# tec_controller_v3.net
KiCad netlist of a schematic drawn in EAGLE
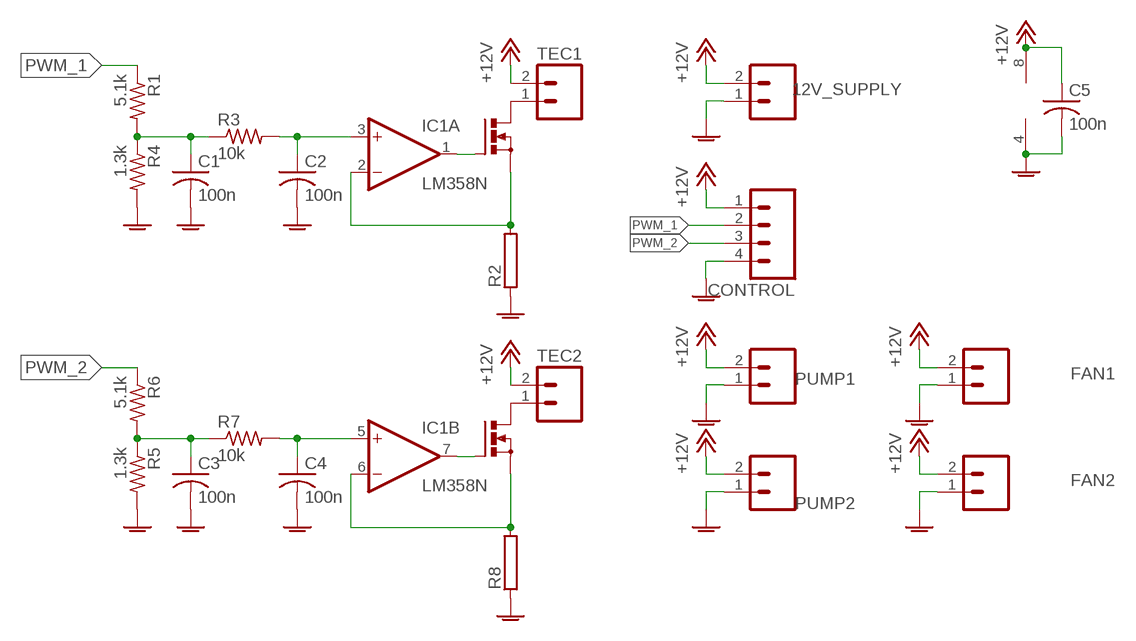
[diagram p0: schematic, sheet 1]

(export (version "E")
  (design (tool "Eeschema 10.0.6"))
  (components
    (comp (ref "12V_SUPPLY")
      (value "M02LOCK_LONGPADS")
      (footprint "eagle-import:1X02_LOCK_LONGPADS")
      (libsource (lib "eagle-import") (part "M02LOCK_LONGPADS"))
    )
    (comp (ref "C1")
      (value "100n")
      (footprint "eagle-import:C0805")
      (libsource (lib "eagle-import") (part "C-USC0805"))
    )
    (comp (ref "C2")
      (value "100n")
      (footprint "eagle-import:C0805")
      (libsource (lib "eagle-import") (part "C-USC0805"))
    )
    (comp (ref "C3")
      (value "100n")
      (footprint "eagle-import:C0805")
      (libsource (lib "eagle-import") (part "C-USC0805"))
    )
    (comp (ref "C4")
      (value "100n")
      (footprint "eagle-import:C0805")
      (libsource (lib "eagle-import") (part "C-USC0805"))
    )
    (comp (ref "C5")
      (value "100n")
      (footprint "eagle-import:C0805")
      (libsource (lib "eagle-import") (part "C-USC0805"))
    )
    (comp (ref "CONTROL")
      (value "M04POLAR")
      (footprint "eagle-import:MOLEX-1X4")
      (libsource (lib "eagle-import") (part "M04POLAR"))
    )
    (comp (ref "FAN1")
      (value "M02LOCK_LONGPADS")
      (footprint "eagle-import:1X02_LOCK_LONGPADS")
      (libsource (lib "eagle-import") (part "M02LOCK_LONGPADS"))
    )
    (comp (ref "FAN2")
      (value "M02LOCK_LONGPADS")
      (footprint "eagle-import:1X02_LOCK_LONGPADS")
      (libsource (lib "eagle-import") (part "M02LOCK_LONGPADS"))
    )
    (comp (ref "IC1")
      (value "LM358N")
      (footprint "eagle-import:DIL08")
      (libsource (lib "eagle-import") (part "LM358N"))
    )
    (comp (ref "PUMP1")
      (value "M02LOCK_LONGPADS")
      (footprint "eagle-import:1X02_LOCK_LONGPADS")
      (libsource (lib "eagle-import") (part "M02LOCK_LONGPADS"))
    )
    (comp (ref "PUMP2")
      (value "M02LOCK_LONGPADS")
      (footprint "eagle-import:1X02_LOCK_LONGPADS")
      (libsource (lib "eagle-import") (part "M02LOCK_LONGPADS"))
    )
    (comp (ref "Q1")
      (value "IRF512")
      (footprint "eagle-import:TO220BV")
      (libsource (lib "eagle-import") (part "IRF512"))
    )
    (comp (ref "Q2")
      (value "IRF512")
      (footprint "eagle-import:TO220BV")
      (libsource (lib "eagle-import") (part "IRF512"))
    )
    (comp (ref "R1")
      (value "5.1k")
      (footprint "eagle-import:M0805")
      (libsource (lib "eagle-import") (part "R-US_M0805"))
    )
    (comp (ref "R2")
      (value "RAC10")
      (footprint "eagle-import:AC10")
      (libsource (lib "eagle-import") (part "RAC10"))
    )
    (comp (ref "R3")
      (value "10k")
      (footprint "eagle-import:M0805")
      (libsource (lib "eagle-import") (part "R-US_M0805"))
    )
    (comp (ref "R4")
      (value "1.3k")
      (footprint "eagle-import:M0805")
      (libsource (lib "eagle-import") (part "R-US_M0805"))
    )
    (comp (ref "R5")
      (value "1.3k")
      (footprint "eagle-import:M0805")
      (libsource (lib "eagle-import") (part "R-US_M0805"))
    )
    (comp (ref "R6")
      (value "5.1k")
      (footprint "eagle-import:M0805")
      (libsource (lib "eagle-import") (part "R-US_M0805"))
    )
    (comp (ref "R7")
      (value "10k")
      (footprint "eagle-import:M0805")
      (libsource (lib "eagle-import") (part "R-US_M0805"))
    )
    (comp (ref "R8")
      (value "RAC10")
      (footprint "eagle-import:AC10")
      (libsource (lib "eagle-import") (part "RAC10"))
    )
    (comp (ref "TEC1")
      (value "M02LOCK_LONGPADS")
      (footprint "eagle-import:1X02_LOCK_LONGPADS")
      (libsource (lib "eagle-import") (part "M02LOCK_LONGPADS"))
    )
    (comp (ref "TEC2")
      (value "M02LOCK_LONGPADS")
      (footprint "eagle-import:1X02_LOCK_LONGPADS")
      (libsource (lib "eagle-import") (part "M02LOCK_LONGPADS"))
    )
  )
  (nets
    (net (code "1") (name "+12V") (class "Default")
      (node (ref "12V_SUPPLY") (pin "2") (pinfunction "2_2") (pintype "passive"))
      (node (ref "C5") (pin "1") (pinfunction "1_1") (pintype "passive"))
      (node (ref "CONTROL") (pin "1") (pinfunction "1_1") (pintype "passive"))
      (node (ref "FAN1") (pin "2") (pinfunction "2_2") (pintype "passive"))
      (node (ref "FAN2") (pin "2") (pinfunction "2_2") (pintype "passive"))
      (node (ref "IC1") (pin "8") (pinfunction "V+_8") (pintype "power_in"))
      (node (ref "PUMP1") (pin "2") (pinfunction "2_2") (pintype "passive"))
      (node (ref "PUMP2") (pin "2") (pinfunction "2_2") (pintype "passive"))
      (node (ref "TEC1") (pin "2") (pinfunction "2_2") (pintype "passive"))
      (node (ref "TEC2") (pin "2") (pinfunction "2_2") (pintype "passive"))
    )
    (net (code "2") (name "GNDA") (class "Default")
      (node (ref "12V_SUPPLY") (pin "1") (pinfunction "1_1") (pintype "passive"))
      (node (ref "C1") (pin "2") (pinfunction "2_2") (pintype "passive"))
      (node (ref "C2") (pin "2") (pinfunction "2_2") (pintype "passive"))
      (node (ref "C3") (pin "2") (pinfunction "2_2") (pintype "passive"))
      (node (ref "C4") (pin "2") (pinfunction "2_2") (pintype "passive"))
      (node (ref "C5") (pin "2") (pinfunction "2_2") (pintype "passive"))
      (node (ref "CONTROL") (pin "4") (pinfunction "4_4") (pintype "passive"))
      (node (ref "FAN1") (pin "1") (pinfunction "1_1") (pintype "passive"))
      (node (ref "FAN2") (pin "1") (pinfunction "1_1") (pintype "passive"))
      (node (ref "IC1") (pin "4") (pinfunction "V-_4") (pintype "power_in"))
      (node (ref "PUMP1") (pin "1") (pinfunction "1_1") (pintype "passive"))
      (node (ref "PUMP2") (pin "1") (pinfunction "1_1") (pintype "passive"))
      (node (ref "R2") (pin "1") (pinfunction "1_1") (pintype "passive"))
      (node (ref "R4") (pin "2") (pinfunction "2_2") (pintype "passive"))
      (node (ref "R5") (pin "2") (pinfunction "2_2") (pintype "passive"))
      (node (ref "R8") (pin "1") (pinfunction "1_1") (pintype "passive"))
    )
    (net (code "3") (name "Net-(C1-Pad1)") (class "Default")
      (node (ref "C1") (pin "1") (pinfunction "1_1") (pintype "passive"))
      (node (ref "R1") (pin "2") (pinfunction "2_2") (pintype "passive"))
      (node (ref "R3") (pin "1") (pinfunction "1_1") (pintype "passive"))
      (node (ref "R4") (pin "1") (pinfunction "1_1") (pintype "passive"))
    )
    (net (code "4") (name "Net-(C3-Pad1)") (class "Default")
      (node (ref "C3") (pin "1") (pinfunction "1_1") (pintype "passive"))
      (node (ref "R5") (pin "1") (pinfunction "1_1") (pintype "passive"))
      (node (ref "R6") (pin "2") (pinfunction "2_2") (pintype "passive"))
      (node (ref "R7") (pin "1") (pinfunction "1_1") (pintype "passive"))
    )
    (net (code "5") (name "Net-(IC1A-+IN)") (class "Default")
      (node (ref "C2") (pin "1") (pinfunction "1_1") (pintype "passive"))
      (node (ref "IC1") (pin "3") (pinfunction "+IN_3") (pintype "input"))
      (node (ref "R3") (pin "2") (pinfunction "2_2") (pintype "passive"))
    )
    (net (code "6") (name "Net-(IC1A--IN)") (class "Default")
      (node (ref "IC1") (pin "2") (pinfunction "-IN_2") (pintype "input"))
      (node (ref "Q1") (pin "S") (pinfunction "S_S") (pintype "passive"))
      (node (ref "R2") (pin "2") (pinfunction "2_2") (pintype "passive"))
    )
    (net (code "7") (name "Net-(IC1A-OUT)") (class "Default")
      (node (ref "IC1") (pin "1") (pinfunction "OUT_1") (pintype "output"))
      (node (ref "Q1") (pin "G") (pinfunction "G_G") (pintype "passive"))
    )
    (net (code "8") (name "Net-(IC1B-+IN)") (class "Default")
      (node (ref "C4") (pin "1") (pinfunction "1_1") (pintype "passive"))
      (node (ref "IC1") (pin "5") (pinfunction "+IN_5") (pintype "input"))
      (node (ref "R7") (pin "2") (pinfunction "2_2") (pintype "passive"))
    )
    (net (code "9") (name "Net-(IC1B--IN)") (class "Default")
      (node (ref "IC1") (pin "6") (pinfunction "-IN_6") (pintype "input"))
      (node (ref "Q2") (pin "S") (pinfunction "S_S") (pintype "passive"))
      (node (ref "R8") (pin "2") (pinfunction "2_2") (pintype "passive"))
    )
    (net (code "10") (name "Net-(IC1B-OUT)") (class "Default")
      (node (ref "IC1") (pin "7") (pinfunction "OUT_7") (pintype "output"))
      (node (ref "Q2") (pin "G") (pinfunction "G_G") (pintype "passive"))
    )
    (net (code "11") (name "Net-(Q1-PadD)") (class "Default")
      (node (ref "Q1") (pin "D") (pinfunction "D_D") (pintype "passive"))
      (node (ref "TEC1") (pin "1") (pinfunction "1_1") (pintype "passive"))
    )
    (net (code "12") (name "Net-(Q2-PadD)") (class "Default")
      (node (ref "Q2") (pin "D") (pinfunction "D_D") (pintype "passive"))
      (node (ref "TEC2") (pin "1") (pinfunction "1_1") (pintype "passive"))
    )
    (net (code "13") (name "PWM_1") (class "Default")
      (node (ref "CONTROL") (pin "2") (pinfunction "2_2") (pintype "passive"))
      (node (ref "R1") (pin "1") (pinfunction "1_1") (pintype "passive"))
    )
    (net (code "14") (name "PWM_2") (class "Default")
      (node (ref "CONTROL") (pin "3") (pinfunction "3_3") (pintype "passive"))
      (node (ref "R6") (pin "1") (pinfunction "1_1") (pintype "passive"))
    )
  )
)
